# ArtixConfig.net
KiCad netlist of a schematic drawn in Altium Designer
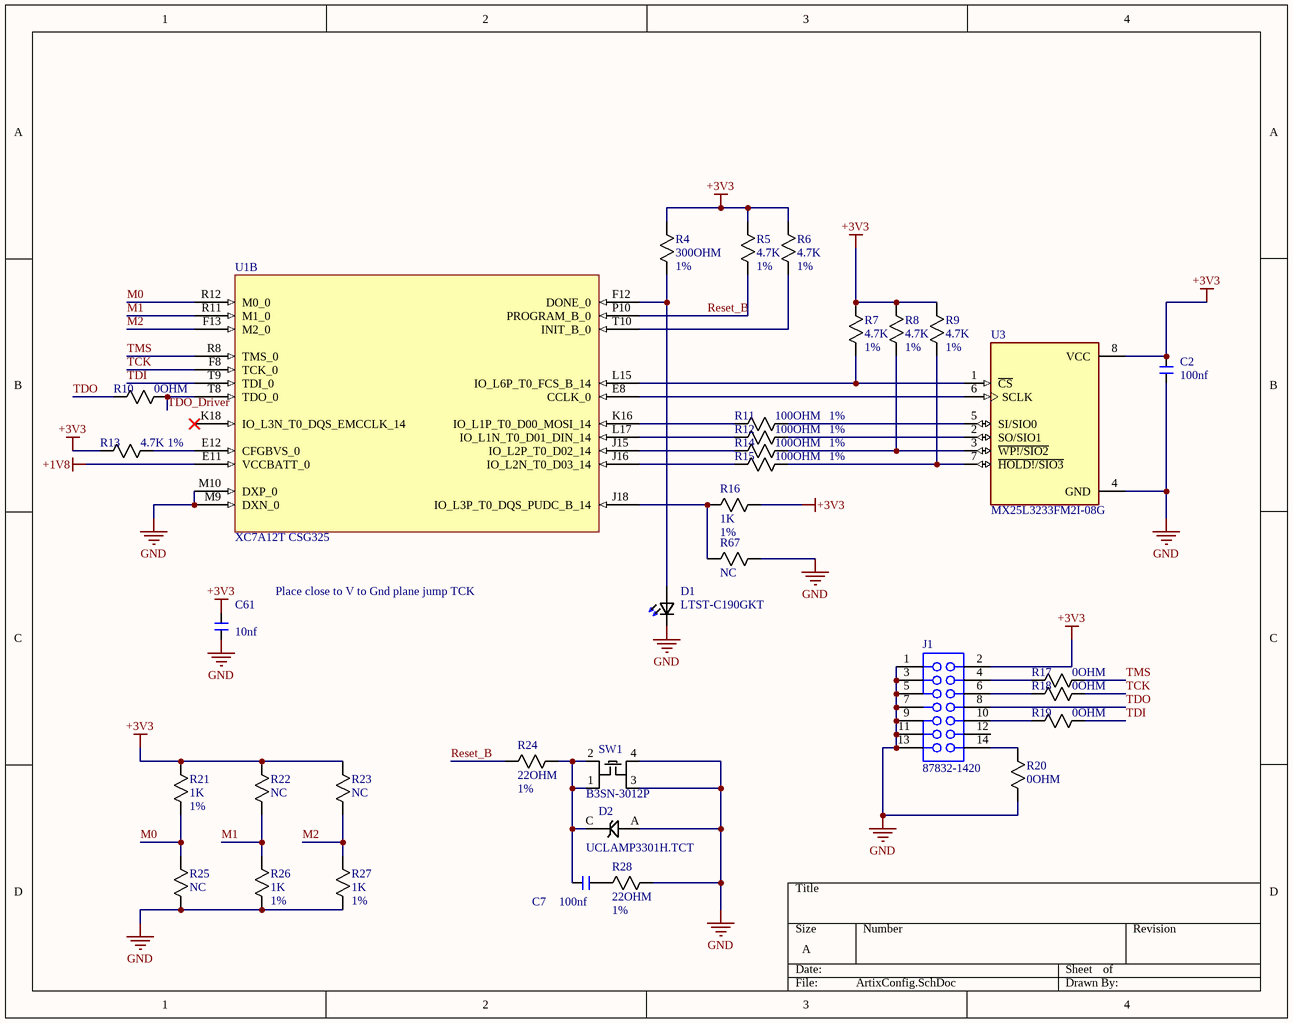
[diagram p0: ArtixConfig.SchDoc]

(export (version "E")
  (design (tool "Eeschema 10.0.6"))
  (components
    (comp (ref "C2")
      (value "100nf")
      (footprint "0402Footprint")
      (description "0402")
      (libsource (lib "Capacitors") (part "100nf_0402"))
    )
    (comp (ref "C7")
      (value "100nf")
      (footprint "0402Footprint")
      (description "0402")
      (libsource (lib "Capacitors") (part "100nf_0402"))
    )
    (comp (ref "C61")
      (value "10nf")
      (footprint "0402Footprint")
      (description "0402")
      (libsource (lib "Capacitors") (part "10nf_0402"))
    )
    (comp (ref "D1")
      (value "LTST-C190GKT")
      (footprint "0603")
      (description "Green 569nm LED Indication - Discrete 2.1V 10mA 0603")
      (fields (field (name "MANUFACTURER") "Lite-On Inc."))
      (libsource (lib "Diodes") (part "LTST-C190GKT"))
    )
    (comp (ref "D2")
      (value "UCLAMP3301H.TCT")
      (footprint "SODFL160X70-2L")
      (description "TVS Diode 3.3V 8V SOD523")
      (libsource (lib "Diodes") (part "UCLAMP3301H.TCT"))
    )
    (comp (ref "J1")
      (value "87832-1420")
      (footprint "MOLEX_87832-1420")
      (description "Connector Header Surface Mount 14 position 0.079 _2.00mm_")
      (fields (field (name "MF") "Molex"))
      (libsource (lib "87832-1420") (part "87832-1420"))
    )
    (comp (ref "R4")
      (value "300OHM")
      (footprint "RES_CRCW_0402")
      (description "0402")
      (fields (field (name "POWER") "1/10W") (field (name "TOLERANCE") "1%"))
      (libsource (lib "Resistors") (part "300OHM_0402"))
    )
    (comp (ref "R5")
      (value "4.7K")
      (footprint "RES_CRCW_0402")
      (description "0402")
      (fields (field (name "TOLERANCE") "1%"))
      (libsource (lib "Resistors") (part "4.7K_0402"))
    )
    (comp (ref "R6")
      (value "4.7K")
      (footprint "RES_CRCW_0402")
      (description "0402")
      (fields (field (name "TOLERANCE") "1%"))
      (libsource (lib "Resistors") (part "4.7K_0402"))
    )
    (comp (ref "R7")
      (value "4.7K")
      (footprint "RES_CRCW_0402")
      (description "0402")
      (fields (field (name "TOLERANCE") "1%"))
      (libsource (lib "Resistors") (part "4.7K_0402"))
    )
    (comp (ref "R8")
      (value "4.7K")
      (footprint "RES_CRCW_0402")
      (description "0402")
      (fields (field (name "TOLERANCE") "1%"))
      (libsource (lib "Resistors") (part "4.7K_0402"))
    )
    (comp (ref "R9")
      (value "4.7K")
      (footprint "RES_CRCW_0402")
      (description "0402")
      (fields (field (name "TOLERANCE") "1%"))
      (libsource (lib "Resistors") (part "4.7K_0402"))
    )
    (comp (ref "R10")
      (value "0OHM")
      (footprint "RES_CRCW_0402")
      (description "0402")
      (libsource (lib "Resistors") (part "0OHM_0402"))
    )
    (comp (ref "R11")
      (value "100OHM")
      (footprint "RES_CRCW_0402")
      (description "0402")
      (fields (field (name "TOLERANCE") "1%"))
      (libsource (lib "Resistors") (part "100OHM_0402"))
    )
    (comp (ref "R12")
      (value "100OHM")
      (footprint "RES_CRCW_0402")
      (description "0402")
      (fields (field (name "TOLERANCE") "1%"))
      (libsource (lib "Resistors") (part "100OHM_0402"))
    )
    (comp (ref "R13")
      (value "4.7K")
      (footprint "RES_CRCW_0402")
      (description "0402")
      (fields (field (name "TOLERANCE") "1%"))
      (libsource (lib "Resistors") (part "4.7K_0402"))
    )
    (comp (ref "R14")
      (value "100OHM")
      (footprint "RES_CRCW_0402")
      (description "0402")
      (fields (field (name "TOLERANCE") "1%"))
      (libsource (lib "Resistors") (part "100OHM_0402"))
    )
    (comp (ref "R15")
      (value "100OHM")
      (footprint "RES_CRCW_0402")
      (description "0402")
      (fields (field (name "TOLERANCE") "1%"))
      (libsource (lib "Resistors") (part "100OHM_0402"))
    )
    (comp (ref "R16")
      (value "1K")
      (footprint "RES_CRCW_0402")
      (description "0402")
      (fields (field (name "TOLERANCE") "1%"))
      (libsource (lib "Resistors") (part "1k_0402"))
    )
    (comp (ref "R17")
      (value "0OHM")
      (footprint "RES_CRCW_0402")
      (description "0402")
      (libsource (lib "Resistors") (part "0OHM_0402"))
    )
    (comp (ref "R18")
      (value "0OHM")
      (footprint "RES_CRCW_0402")
      (description "0402")
      (libsource (lib "Resistors") (part "0OHM_0402"))
    )
    (comp (ref "R19")
      (value "0OHM")
      (footprint "RES_CRCW_0402")
      (description "0402")
      (libsource (lib "Resistors") (part "0OHM_0402"))
    )
    (comp (ref "R20")
      (value "0OHM")
      (footprint "RES_CRCW_0402")
      (description "0402")
      (libsource (lib "Resistors") (part "0OHM_0402"))
    )
    (comp (ref "R21")
      (value "1K")
      (footprint "RES_CRCW_0402")
      (description "0402")
      (fields (field (name "TOLERANCE") "1%"))
      (libsource (lib "Resistors") (part "1k_0402"))
    )
    (comp (ref "R22") (value "NC") (footprint "RES_CRCW_0402") (libsource (lib "Resistors") (part "NC_0402")))
    (comp (ref "R23") (value "NC") (footprint "RES_CRCW_0402") (libsource (lib "Resistors") (part "NC_0402")))
    (comp (ref "R24")
      (value "22OHM")
      (footprint "RES_CRCW_0402")
      (description "0402")
      (fields (field (name "TOLERANCE") "1%"))
      (libsource (lib "Resistors") (part "22OHM_0402"))
    )
    (comp (ref "R25") (value "NC") (footprint "RES_CRCW_0402") (libsource (lib "Resistors") (part "NC_0402")))
    (comp (ref "R26")
      (value "1K")
      (footprint "RES_CRCW_0402")
      (description "0402")
      (fields (field (name "TOLERANCE") "1%"))
      (libsource (lib "Resistors") (part "1k_0402"))
    )
    (comp (ref "R27")
      (value "1K")
      (footprint "RES_CRCW_0402")
      (description "0402")
      (fields (field (name "TOLERANCE") "1%"))
      (libsource (lib "Resistors") (part "1k_0402"))
    )
    (comp (ref "R28")
      (value "22OHM")
      (footprint "RES_CRCW_0402")
      (description "0402")
      (fields (field (name "TOLERANCE") "1%"))
      (libsource (lib "Resistors") (part "22OHM_0402"))
    )
    (comp (ref "R67") (value "NC") (footprint "RES_CRCW_0402") (libsource (lib "Resistors") (part "NC_0402")))
    (comp (ref "SW1")
      (value "B3SN-3012P")
      (footprint "B3SN-3012P")
      (fields (field (name "MANUFACTURER") "Omron"))
      (libsource (lib "Switches") (part "B3SN-3012P"))
    )
    (comp (ref "U1")
      (value "XC7A12T CSG325")
      (footprint "BGA324C80P18X18_1500X1500X150")
      (libsource (lib "XC7A12T_1CPG238I") (part "XC7A12T_1CSG325I"))
    )
    (comp (ref "U3")
      (value "MX25L3233FM2I-08G")
      (footprint "SOIC127P790X216-8N_MX25L3233FM2I-08G")
      (description "FLASH - NOR Memory IC 32Mb _8M x 4_ SPI - Quad I/O 133MHz 8-SOP")
      (fields (field (name "MF") "Macronix"))
      (libsource (lib "MX25L3233FM2I-08G") (part "MX25L3233FM2I-08G"))
    )
  )
  (nets
    (net (code "1") (name "+1V8") (class "Default")
      (node (ref "U1") (pin "E11") (pinfunction "VCCBATT_0_E11") (pintype "input"))
    )
    (net (code "2") (name "+3V3") (class "Default")
      (node (ref "C2") (pin "1") (pinfunction "1_1") (pintype "passive"))
      (node (ref "C61") (pin "1") (pinfunction "1_1") (pintype "passive"))
      (node (ref "J1") (pin "2") (pinfunction "2_2") (pintype "passive"))
      (node (ref "R13") (pin "2") (pinfunction "2_2") (pintype "passive"))
      (node (ref "R16") (pin "1") (pinfunction "1_1") (pintype "passive"))
      (node (ref "R21") (pin "1") (pinfunction "1_1") (pintype "passive"))
      (node (ref "R22") (pin "1") (pinfunction "1_1") (pintype "passive"))
      (node (ref "R23") (pin "1") (pinfunction "1_1") (pintype "passive"))
      (node (ref "R4") (pin "1") (pinfunction "1_1") (pintype "passive"))
      (node (ref "R5") (pin "1") (pinfunction "1_1") (pintype "passive"))
      (node (ref "R6") (pin "1") (pinfunction "1_1") (pintype "passive"))
      (node (ref "R7") (pin "1") (pinfunction "1_1") (pintype "passive"))
      (node (ref "R8") (pin "1") (pinfunction "1_1") (pintype "passive"))
      (node (ref "R9") (pin "1") (pinfunction "1_1") (pintype "passive"))
      (node (ref "U3") (pin "8") (pinfunction "VCC_8") (pintype "power_in"))
    )
    (net (code "3") (name "/M0") (class "Default")
      (node (ref "R21") (pin "2") (pinfunction "2_2") (pintype "passive"))
      (node (ref "R25") (pin "1") (pinfunction "1_1") (pintype "passive"))
      (node (ref "U1") (pin "R12") (pinfunction "M0_0_R12") (pintype "input"))
    )
    (net (code "4") (name "/M1") (class "Default")
      (node (ref "R22") (pin "2") (pinfunction "2_2") (pintype "passive"))
      (node (ref "R26") (pin "1") (pinfunction "1_1") (pintype "passive"))
      (node (ref "U1") (pin "R11") (pinfunction "M1_0_R11") (pintype "input"))
    )
    (net (code "5") (name "/M2") (class "Default")
      (node (ref "R23") (pin "2") (pinfunction "2_2") (pintype "passive"))
      (node (ref "R27") (pin "1") (pinfunction "1_1") (pintype "passive"))
      (node (ref "U1") (pin "F13") (pinfunction "M2_0_F13") (pintype "input"))
    )
    (net (code "6") (name "/Reset_B") (class "Default")
      (node (ref "R24") (pin "2") (pinfunction "2_2") (pintype "passive"))
      (node (ref "R5") (pin "2") (pinfunction "2_2") (pintype "passive"))
      (node (ref "U1") (pin "P10") (pinfunction "PROGRAM_B_0_P10") (pintype "input"))
    )
    (net (code "7") (name "/TCK") (class "Default")
      (node (ref "R18") (pin "1") (pinfunction "1_1") (pintype "passive"))
      (node (ref "U1") (pin "F8") (pinfunction "TCK_0_F8") (pintype "input"))
    )
    (net (code "8") (name "/TDI") (class "Default")
      (node (ref "R19") (pin "1") (pinfunction "1_1") (pintype "passive"))
      (node (ref "U1") (pin "T9") (pinfunction "TDI_0_T9") (pintype "input"))
    )
    (net (code "9") (name "/TDO") (class "Default")
      (node (ref "J1") (pin "8") (pinfunction "8_8") (pintype "passive"))
      (node (ref "R10") (pin "2") (pinfunction "2_2") (pintype "passive"))
    )
    (net (code "10") (name "/TDO_Driver") (class "Default")
      (node (ref "R10") (pin "1") (pinfunction "1_1") (pintype "passive"))
      (node (ref "U1") (pin "T8") (pinfunction "TDO_0_T8") (pintype "input"))
    )
    (net (code "11") (name "/TMS") (class "Default")
      (node (ref "R17") (pin "1") (pinfunction "1_1") (pintype "passive"))
      (node (ref "U1") (pin "R8") (pinfunction "TMS_0_R8") (pintype "input"))
    )
    (net (code "12") (name "GND") (class "Default")
      (node (ref "C2") (pin "2") (pinfunction "2_2") (pintype "passive"))
      (node (ref "C61") (pin "2") (pinfunction "2_2") (pintype "passive"))
      (node (ref "D1") (pin "1") (pinfunction "K2_1") (pintype "passive"))
      (node (ref "D2") (pin "A") (pintype "passive"))
      (node (ref "J1") (pin "1") (pinfunction "1_1") (pintype "passive"))
      (node (ref "J1") (pin "11") (pinfunction "11_11") (pintype "passive"))
      (node (ref "J1") (pin "13") (pinfunction "13_13") (pintype "passive"))
      (node (ref "J1") (pin "3") (pinfunction "3_3") (pintype "passive"))
      (node (ref "J1") (pin "5") (pinfunction "5_5") (pintype "passive"))
      (node (ref "J1") (pin "7") (pinfunction "7_7") (pintype "passive"))
      (node (ref "J1") (pin "9") (pinfunction "9_9") (pintype "passive"))
      (node (ref "R20") (pin "1") (pinfunction "1_1") (pintype "passive"))
      (node (ref "R25") (pin "2") (pinfunction "2_2") (pintype "passive"))
      (node (ref "R26") (pin "2") (pinfunction "2_2") (pintype "passive"))
      (node (ref "R27") (pin "2") (pinfunction "2_2") (pintype "passive"))
      (node (ref "R28") (pin "1") (pinfunction "1_1") (pintype "passive"))
      (node (ref "R67") (pin "2") (pinfunction "2_2") (pintype "passive"))
      (node (ref "SW1") (pin "3") (pintype "passive"))
      (node (ref "SW1") (pin "4") (pintype "passive"))
      (node (ref "U1") (pin "M10") (pinfunction "DXP_0_M10") (pintype "input"))
      (node (ref "U1") (pin "M9") (pinfunction "DXN_0_M9") (pintype "input"))
      (node (ref "U3") (pin "4") (pinfunction "GND_4") (pintype "power_in"))
    )
    (net (code "13") (name "Net-(C7-Pad1)") (class "Default")
      (node (ref "C7") (pin "1") (pinfunction "1_1") (pintype "passive"))
      (node (ref "R28") (pin "2") (pinfunction "2_2") (pintype "passive"))
    )
    (net (code "14") (name "Net-(C7-Pad2)") (class "Default")
      (node (ref "C7") (pin "2") (pinfunction "2_2") (pintype "passive"))
      (node (ref "D2") (pin "C") (pintype "passive"))
      (node (ref "R24") (pin "1") (pinfunction "1_1") (pintype "passive"))
      (node (ref "SW1") (pin "1") (pintype "passive"))
      (node (ref "SW1") (pin "2") (pintype "passive"))
    )
    (net (code "15") (name "Net-(D1-A2)") (class "Default")
      (node (ref "D1") (pin "2") (pinfunction "A2_2") (pintype "passive"))
      (node (ref "R4") (pin "2") (pinfunction "2_2") (pintype "passive"))
      (node (ref "U1") (pin "F12") (pinfunction "DONE_0_F12") (pintype "input"))
    )
    (net (code "16") (name "Net-(J1-Pad4)") (class "Default")
      (node (ref "J1") (pin "4") (pinfunction "4_4") (pintype "passive"))
      (node (ref "R17") (pin "2") (pinfunction "2_2") (pintype "passive"))
    )
    (net (code "17") (name "Net-(J1-Pad6)") (class "Default")
      (node (ref "J1") (pin "6") (pinfunction "6_6") (pintype "passive"))
      (node (ref "R18") (pin "2") (pinfunction "2_2") (pintype "passive"))
    )
    (net (code "18") (name "Net-(J1-Pad10)") (class "Default")
      (node (ref "J1") (pin "10") (pinfunction "10_10") (pintype "passive"))
      (node (ref "R19") (pin "2") (pinfunction "2_2") (pintype "passive"))
    )
    (net (code "19") (name "Net-(J1-Pad14)") (class "Default")
      (node (ref "J1") (pin "14") (pinfunction "14_14") (pintype "passive"))
      (node (ref "R20") (pin "2") (pinfunction "2_2") (pintype "passive"))
    )
    (net (code "20") (name "Net-(U1B-CCLK_0)") (class "Default")
      (node (ref "U1") (pin "E8") (pinfunction "CCLK_0_E8") (pintype "input"))
      (node (ref "U3") (pin "6") (pinfunction "SCLK_6") (pintype "input"))
    )
    (net (code "21") (name "Net-(U1B-CFGBVS_0)") (class "Default")
      (node (ref "R13") (pin "1") (pinfunction "1_1") (pintype "passive"))
      (node (ref "U1") (pin "E12") (pinfunction "CFGBVS_0_E12") (pintype "input"))
    )
    (net (code "22") (name "Net-(U1B-INIT_B_0)") (class "Default")
      (node (ref "R6") (pin "2") (pinfunction "2_2") (pintype "passive"))
      (node (ref "U1") (pin "T10") (pinfunction "INIT_B_0_T10") (pintype "input"))
    )
    (net (code "23") (name "Net-(U1B-IO_L1N_T0_D01_DIN_14)") (class "Default")
      (node (ref "R12") (pin "2") (pinfunction "2_2") (pintype "passive"))
      (node (ref "U1") (pin "L17") (pinfunction "IO_L1N_T0_D01_DIN_14_L17") (pintype "input"))
    )
    (net (code "24") (name "Net-(U1B-IO_L1P_T0_D00_MOSI_14)") (class "Default")
      (node (ref "R11") (pin "2") (pinfunction "2_2") (pintype "passive"))
      (node (ref "U1") (pin "K16") (pinfunction "IO_L1P_T0_D00_MOSI_14_K16") (pintype "input"))
    )
    (net (code "25") (name "Net-(U1B-IO_L2N_T0_D03_14)") (class "Default")
      (node (ref "R15") (pin "2") (pinfunction "2_2") (pintype "passive"))
      (node (ref "U1") (pin "J16") (pinfunction "IO_L2N_T0_D03_14_J16") (pintype "input"))
    )
    (net (code "26") (name "Net-(U1B-IO_L2P_T0_D02_14)") (class "Default")
      (node (ref "R14") (pin "2") (pinfunction "2_2") (pintype "passive"))
      (node (ref "U1") (pin "J15") (pinfunction "IO_L2P_T0_D02_14_J15") (pintype "input"))
    )
    (net (code "27") (name "Net-(U1B-IO_L3P_T0_DQS_PUDC_B_14)") (class "Default")
      (node (ref "R16") (pin "2") (pinfunction "2_2") (pintype "passive"))
      (node (ref "R67") (pin "1") (pinfunction "1_1") (pintype "passive"))
      (node (ref "U1") (pin "J18") (pinfunction "IO_L3P_T0_DQS_PUDC_B_14_J18") (pintype "input"))
    )
    (net (code "28") (name "Net-(U1B-IO_L6P_T0_FCS_B_14)") (class "Default")
      (node (ref "R7") (pin "2") (pinfunction "2_2") (pintype "passive"))
      (node (ref "U1") (pin "L15") (pinfunction "IO_L6P_T0_FCS_B_14_L15") (pintype "input"))
      (node (ref "U3") (pin "1") (pinfunction "~{CS}_1") (pintype "input"))
    )
    (net (code "29") (name "Net-(U3-SI{slash}SIO0)") (class "Default")
      (node (ref "R11") (pin "1") (pinfunction "1_1") (pintype "passive"))
      (node (ref "U3") (pin "5") (pinfunction "SI/SIO0_5") (pintype "bidirectional"))
    )
    (net (code "30") (name "Net-(U3-SO{slash}SIO1)") (class "Default")
      (node (ref "R12") (pin "1") (pinfunction "1_1") (pintype "passive"))
      (node (ref "U3") (pin "2") (pinfunction "SO/SIO1_2") (pintype "bidirectional"))
    )
    (net (code "31") (name "Net-(U3-~{HOLD!{slash}SIO3})") (class "Default")
      (node (ref "R15") (pin "1") (pinfunction "1_1") (pintype "passive"))
      (node (ref "R9") (pin "2") (pinfunction "2_2") (pintype "passive"))
      (node (ref "U3") (pin "7") (pinfunction "~{HOLD!/SIO3}_7") (pintype "bidirectional"))
    )
    (net (code "32") (name "Net-(U3-~{WP!{slash}SIO2})") (class "Default")
      (node (ref "R14") (pin "1") (pinfunction "1_1") (pintype "passive"))
      (node (ref "R8") (pin "2") (pinfunction "2_2") (pintype "passive"))
      (node (ref "U3") (pin "3") (pinfunction "~{WP!/SIO2}_3") (pintype "bidirectional"))
    )
    (net (code "33") (name "unconnected-(J1-Pad12)") (class "Default")
      (node (ref "J1") (pin "12") (pinfunction "12_12") (pintype "passive"))
    )
    (net (code "34") (name "unconnected-(U1B-IO_L3N_T0_DQS_EMCCLK_14-PadK18)") (class "Default")
      (node (ref "U1") (pin "K18") (pinfunction "IO_L3N_T0_DQS_EMCCLK_14_K18") (pintype "input+no_connect"))
    )
  )
)
